# Business_Card5x.net
KiCad netlist of a schematic drawn in EAGLE
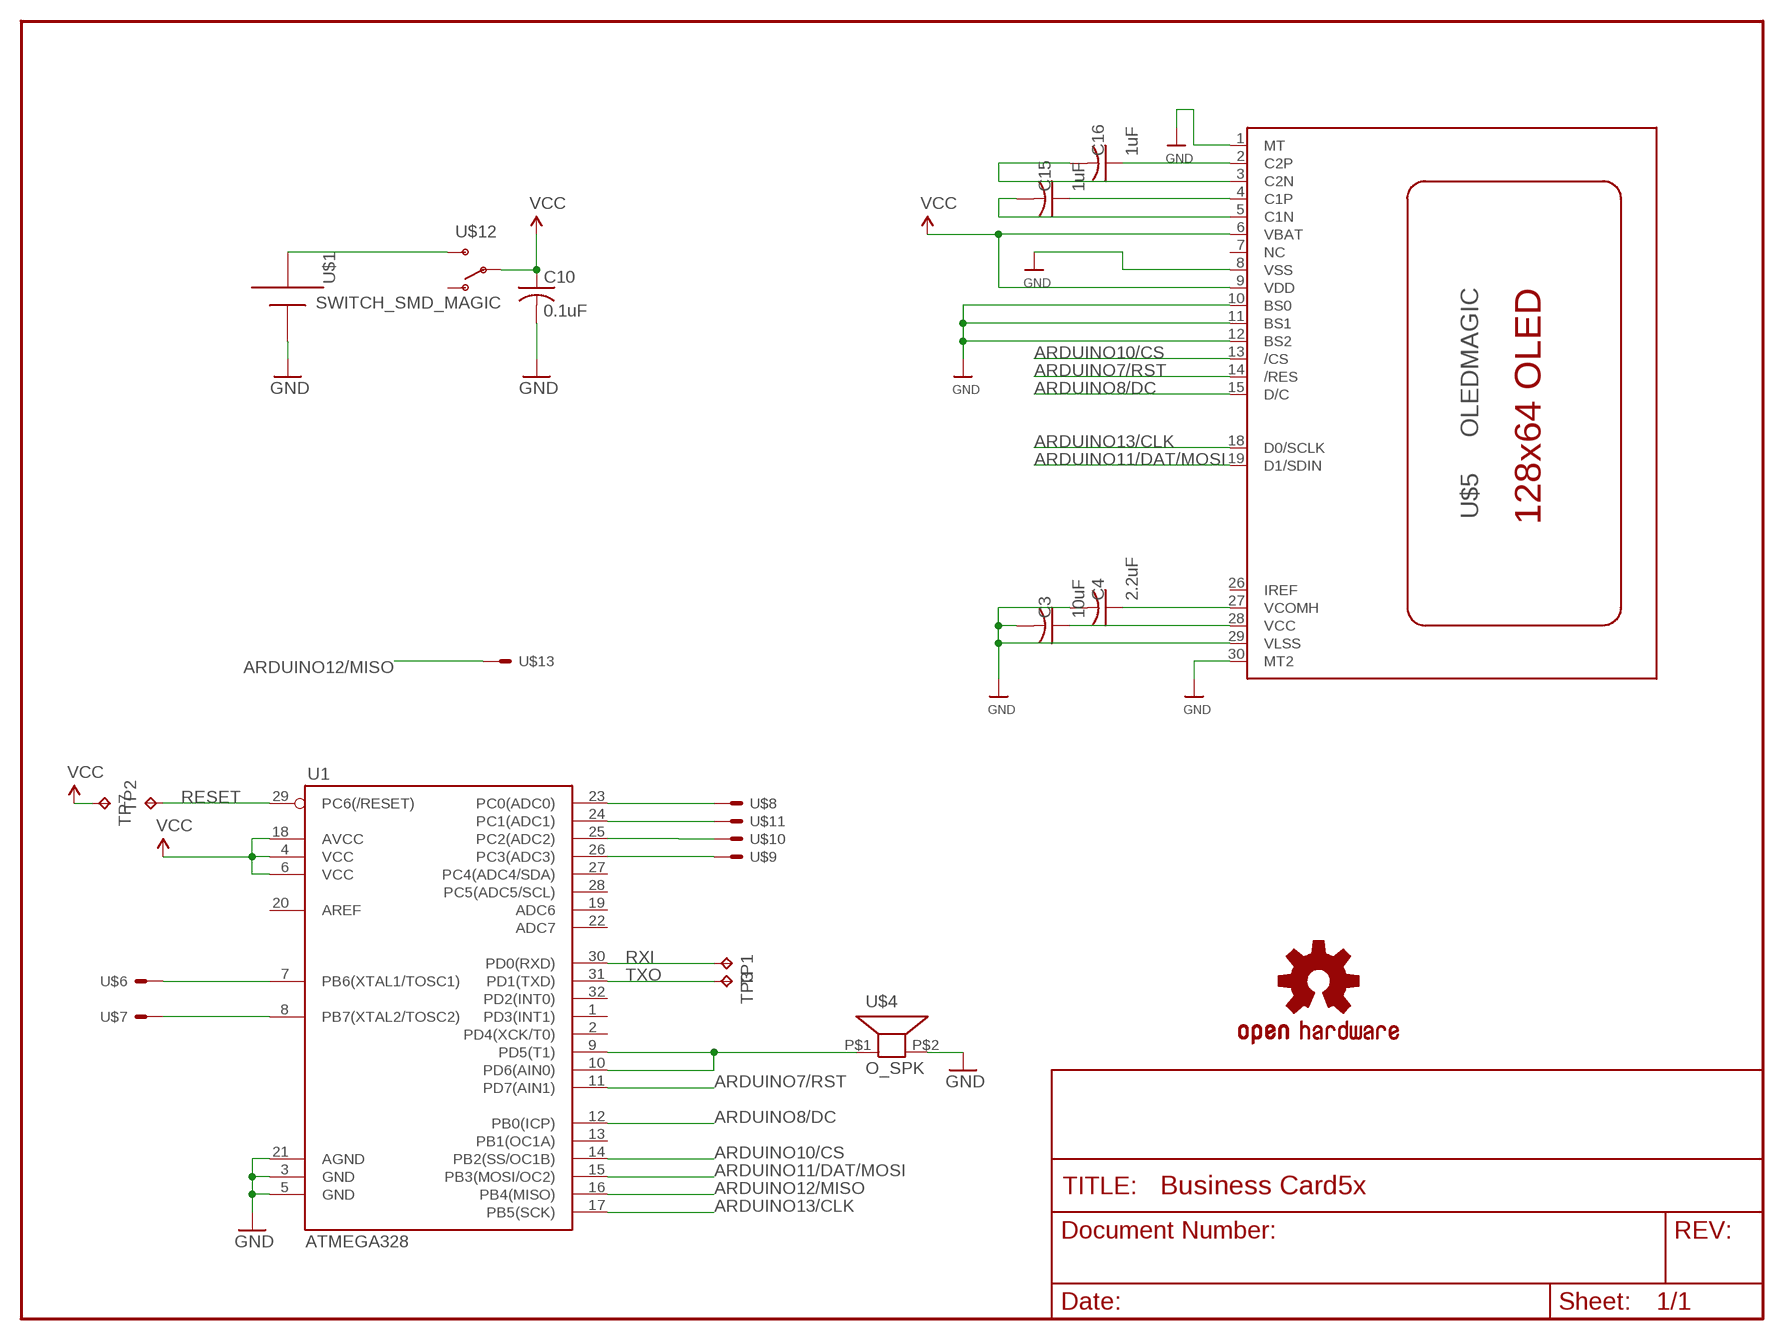
[diagram p0: schematic, sheet 1]

(export (version "E")
  (design (tool "Eeschema 10.0.6"))
  (components
    (comp (ref "C3")
      (value "10uF")
      (footprint "eagle-import:1MILCIR")
      (libsource (lib "eagle-import") (part "O_CAP0805"))
    )
    (comp (ref "C4")
      (value "2.2uF")
      (footprint "eagle-import:1MILCIR")
      (libsource (lib "eagle-import") (part "O_CAP0805"))
    )
    (comp (ref "C10")
      (value "0.1uF")
      (footprint "eagle-import:1MILCIR")
      (libsource (lib "eagle-import") (part "O_CAP0805"))
    )
    (comp (ref "C15")
      (value "1uF")
      (footprint "eagle-import:1MILCIR")
      (libsource (lib "eagle-import") (part "O_CAP0805"))
    )
    (comp (ref "C16")
      (value "1uF")
      (footprint "eagle-import:1MILCIR")
      (libsource (lib "eagle-import") (part "O_CAP0805"))
    )
    (comp (ref "TP1")
      (value "TPTP14R")
      (footprint "eagle-import:TP14R")
      (libsource (lib "eagle-import") (part "TPTP14R"))
    )
    (comp (ref "TP2")
      (value "TPTP14R")
      (footprint "eagle-import:TP14R")
      (libsource (lib "eagle-import") (part "TPTP14R"))
    )
    (comp (ref "TP3")
      (value "TPTP14R")
      (footprint "eagle-import:TP14R")
      (libsource (lib "eagle-import") (part "TPTP14R"))
    )
    (comp (ref "TP7")
      (value "TPTP08SQ")
      (footprint "eagle-import:TP08SQ")
      (libsource (lib "eagle-import") (part "TPTP08SQ"))
    )
    (comp (ref "U$1")
      (value "2016BAT")
      (footprint "eagle-import:CR2016")
      (libsource (lib "eagle-import") (part "2016BAT"))
    )
    (comp (ref "U$3")
      (value "OSHW-LOGOS")
      (footprint "eagle-import:OSHW-LOGO-S")
      (libsource (lib "eagle-import") (part "OSHW-LOGOS"))
    )
    (comp (ref "U$4")
      (value "O_SPK")
      (footprint "eagle-import:O_SPK")
      (libsource (lib "eagle-import") (part "O_SPK"))
    )
    (comp (ref "U$5")
      (value "OLEDMAGIC")
      (footprint "eagle-import:1X30OLED")
      (libsource (lib "eagle-import") (part "OLEDMAGIC"))
    )
    (comp (ref "U$6")
      (value "CAP_BUTTON")
      (footprint "eagle-import:CAPBUTTON")
      (libsource (lib "eagle-import") (part "CAP_BUTTON"))
    )
    (comp (ref "U$7")
      (value "CAP_BUTTON")
      (footprint "eagle-import:CAPBUTTON")
      (libsource (lib "eagle-import") (part "CAP_BUTTON"))
    )
    (comp (ref "U$8")
      (value "CAP_DPAD")
      (footprint "eagle-import:DPAD")
      (libsource (lib "eagle-import") (part "CAP_DPAD"))
    )
    (comp (ref "U$9")
      (value "CAP_DPAD")
      (footprint "eagle-import:DPAD")
      (libsource (lib "eagle-import") (part "CAP_DPAD"))
    )
    (comp (ref "U$10")
      (value "CAP_DPAD")
      (footprint "eagle-import:DPAD")
      (libsource (lib "eagle-import") (part "CAP_DPAD"))
    )
    (comp (ref "U$11")
      (value "CAP_DPAD")
      (footprint "eagle-import:DPAD")
      (libsource (lib "eagle-import") (part "CAP_DPAD"))
    )
    (comp (ref "U$12")
      (value "SWITCH_SMD_MAGIC")
      (footprint "eagle-import:SWITCH_SMD_SUNKEN")
      (libsource (lib "eagle-import") (part "SWITCH_SMD_MAGIC"))
    )
    (comp (ref "U$13")
      (value "VERT_TEST")
      (footprint "eagle-import:VERT_TEST")
      (libsource (lib "eagle-import") (part "VERT_TEST"))
    )
    (comp (ref "U1")
      (value "ATMEGA328")
      (footprint "eagle-import:TQFP32")
      (libsource (lib "eagle-import") (part "O_ATMEGA328_32"))
    )
  )
  (nets
    (net (code "1") (name "/ARDUINO7{slash}RST") (class "Default")
      (node (ref "U$5") (pin "14") (pinfunction "/RES_14") (pintype "input"))
      (node (ref "U1") (pin "11") (pinfunction "PD7(AIN1)_11") (pintype "bidirectional"))
    )
    (net (code "2") (name "/ARDUINO8{slash}DC") (class "Default")
      (node (ref "U$5") (pin "15") (pinfunction "D/C_15") (pintype "input"))
      (node (ref "U1") (pin "12") (pinfunction "PB0(ICP)_12") (pintype "bidirectional"))
    )
    (net (code "3") (name "/ARDUINO10{slash}CS") (class "Default")
      (node (ref "U$5") (pin "13") (pinfunction "/CS_13") (pintype "input"))
      (node (ref "U1") (pin "14") (pinfunction "PB2(SS/OC1B)_14") (pintype "bidirectional"))
    )
    (net (code "4") (name "/ARDUINO11{slash}DAT{slash}MOSI") (class "Default")
      (node (ref "U$5") (pin "19") (pinfunction "D1/SDIN_19") (pintype "bidirectional"))
      (node (ref "U1") (pin "15") (pinfunction "PB3(MOSI/OC2)_15") (pintype "bidirectional"))
    )
    (net (code "5") (name "/ARDUINO12{slash}MISO") (class "Default")
      (node (ref "U$13") (pin "P$1") (pinfunction "S_P$1") (pintype "passive"))
      (node (ref "U1") (pin "16") (pinfunction "PB4(MISO)_16") (pintype "bidirectional"))
    )
    (net (code "6") (name "/ARDUINO13{slash}CLK") (class "Default")
      (node (ref "U$5") (pin "18") (pinfunction "D0/SCLK_18") (pintype "bidirectional"))
      (node (ref "U1") (pin "17") (pinfunction "PB5(SCK)_17") (pintype "bidirectional"))
    )
    (net (code "7") (name "/RESET") (class "Default")
      (node (ref "TP2") (pin "TP") (pinfunction "TP_TP") (pintype "input"))
      (node (ref "U1") (pin "29") (pinfunction "PC6(/RESET)_29") (pintype "bidirectional"))
    )
    (net (code "8") (name "/RXI") (class "Default")
      (node (ref "TP1") (pin "TP") (pinfunction "TP_TP") (pintype "input"))
      (node (ref "U1") (pin "30") (pinfunction "PD0(RXD)_30") (pintype "bidirectional"))
    )
    (net (code "9") (name "/TXO") (class "Default")
      (node (ref "TP3") (pin "TP") (pinfunction "TP_TP") (pintype "input"))
      (node (ref "U1") (pin "31") (pinfunction "PD1(TXD)_31") (pintype "bidirectional"))
    )
    (net (code "10") (name "GND") (class "Default")
      (node (ref "C10") (pin "P$2") (pinfunction "2_P$2") (pintype "passive"))
      (node (ref "C3") (pin "P$2") (pinfunction "2_P$2") (pintype "passive"))
      (node (ref "C4") (pin "P$2") (pinfunction "2_P$2") (pintype "passive"))
      (node (ref "U$1") (pin "P$1") (pinfunction "+_P$1") (pintype "bidirectional"))
      (node (ref "U$4") (pin "P$2") (pinfunction "2_P$2") (pintype "passive"))
      (node (ref "U$5") (pin "1") (pinfunction "MT_1") (pintype "input"))
      (node (ref "U$5") (pin "10") (pinfunction "BS0_10") (pintype "input"))
      (node (ref "U$5") (pin "11") (pinfunction "BS1_11") (pintype "input"))
      (node (ref "U$5") (pin "12") (pinfunction "BS2_12") (pintype "input"))
      (node (ref "U$5") (pin "29") (pinfunction "VLSS_29") (pintype "power_in"))
      (node (ref "U$5") (pin "30") (pinfunction "MT2_30") (pintype "input"))
      (node (ref "U$5") (pin "8") (pinfunction "VSS_8") (pintype "power_in"))
      (node (ref "U1") (pin "21") (pinfunction "AGND_21") (pintype "bidirectional"))
      (node (ref "U1") (pin "3") (pinfunction "GND_3") (pintype "bidirectional"))
      (node (ref "U1") (pin "5") (pinfunction "GND_5") (pintype "bidirectional"))
    )
    (net (code "11") (name "Net-(C3-1)") (class "Default")
      (node (ref "C3") (pin "P$1") (pinfunction "1_P$1") (pintype "passive"))
      (node (ref "U$5") (pin "28") (pinfunction "VCC_28") (pintype "power_in"))
    )
    (net (code "12") (name "Net-(C4-1)") (class "Default")
      (node (ref "C4") (pin "P$1") (pinfunction "1_P$1") (pintype "passive"))
      (node (ref "U$5") (pin "27") (pinfunction "VCOMH_27") (pintype "output"))
    )
    (net (code "13") (name "Net-(C15-1)") (class "Default")
      (node (ref "C15") (pin "P$1") (pinfunction "1_P$1") (pintype "passive"))
      (node (ref "U$5") (pin "4") (pinfunction "C1P_4") (pintype "input"))
    )
    (net (code "14") (name "Net-(C15-2)") (class "Default")
      (node (ref "C15") (pin "P$2") (pinfunction "2_P$2") (pintype "passive"))
      (node (ref "U$5") (pin "5") (pinfunction "C1N_5") (pintype "input"))
    )
    (net (code "15") (name "Net-(C16-1)") (class "Default")
      (node (ref "C16") (pin "P$1") (pinfunction "1_P$1") (pintype "passive"))
      (node (ref "U$5") (pin "2") (pinfunction "C2P_2") (pintype "input"))
    )
    (net (code "16") (name "Net-(C16-2)") (class "Default")
      (node (ref "C16") (pin "P$2") (pinfunction "2_P$2") (pintype "passive"))
      (node (ref "U$5") (pin "3") (pinfunction "C2N_3") (pintype "input"))
    )
    (net (code "17") (name "Net-(U$1--)") (class "Default")
      (node (ref "U$1") (pin "P$2") (pinfunction "-_P$2") (pintype "bidirectional"))
      (node (ref "U$12") (pin "3") (pinfunction "S_3") (pintype "passive"))
    )
    (net (code "18") (name "Net-(U$4-1)") (class "Default")
      (node (ref "U$4") (pin "P$1") (pinfunction "1_P$1") (pintype "passive"))
      (node (ref "U1") (pin "10") (pinfunction "PD6(AIN0)_10") (pintype "bidirectional"))
      (node (ref "U1") (pin "9") (pinfunction "PD5(T1)_9") (pintype "bidirectional"))
    )
    (net (code "19") (name "Net-(U$8-S)") (class "Default")
      (node (ref "U$8") (pin "P$1") (pinfunction "S_P$1") (pintype "passive"))
      (node (ref "U1") (pin "23") (pinfunction "PC0(ADC0)_23") (pintype "bidirectional"))
    )
    (net (code "20") (name "Net-(U$9-S)") (class "Default")
      (node (ref "U$9") (pin "P$1") (pinfunction "S_P$1") (pintype "passive"))
      (node (ref "U1") (pin "26") (pinfunction "PC3(ADC3)_26") (pintype "bidirectional"))
    )
    (net (code "21") (name "Net-(U$10-S)") (class "Default")
      (node (ref "U$10") (pin "P$1") (pinfunction "S_P$1") (pintype "passive"))
      (node (ref "U1") (pin "25") (pinfunction "PC2(ADC2)_25") (pintype "bidirectional"))
    )
    (net (code "22") (name "Net-(U$11-S)") (class "Default")
      (node (ref "U$11") (pin "P$1") (pinfunction "S_P$1") (pintype "passive"))
      (node (ref "U1") (pin "24") (pinfunction "PC1(ADC1)_24") (pintype "bidirectional"))
    )
    (net (code "23") (name "Net-(U1-PB6(XTAL1{slash}TOSC1))") (class "Default")
      (node (ref "U$6") (pin "P$1") (pinfunction "S_P$1") (pintype "passive"))
      (node (ref "U$6") (pin "P$2") (pinfunction "S_P$2") (pintype "passive"))
      (node (ref "U1") (pin "7") (pinfunction "PB6(XTAL1/TOSC1)_7") (pintype "bidirectional"))
    )
    (net (code "24") (name "Net-(U1-PB7(XTAL2{slash}TOSC2))") (class "Default")
      (node (ref "U$7") (pin "P$1") (pinfunction "S_P$1") (pintype "passive"))
      (node (ref "U$7") (pin "P$2") (pinfunction "S_P$2") (pintype "passive"))
      (node (ref "U1") (pin "8") (pinfunction "PB7(XTAL2/TOSC2)_8") (pintype "bidirectional"))
    )
    (net (code "25") (name "VCC") (class "Default")
      (node (ref "C10") (pin "P$1") (pinfunction "1_P$1") (pintype "passive"))
      (node (ref "TP7") (pin "TP") (pinfunction "TP_TP") (pintype "input"))
      (node (ref "U$12") (pin "2") (pinfunction "P_2") (pintype "passive"))
      (node (ref "U$5") (pin "6") (pinfunction "VBAT_6") (pintype "input"))
      (node (ref "U$5") (pin "9") (pinfunction "VDD_9") (pintype "power_in"))
      (node (ref "U1") (pin "18") (pinfunction "AVCC_18") (pintype "bidirectional"))
      (node (ref "U1") (pin "4") (pinfunction "VCC_4") (pintype "bidirectional"))
      (node (ref "U1") (pin "6") (pinfunction "VCC_6") (pintype "bidirectional"))
    )
    (net (code "26") (name "unconnected-(U$5-IREF-Pad26)") (class "Default")
      (node (ref "U$5") (pin "26") (pinfunction "IREF_26") (pintype "input"))
    )
    (net (code "27") (name "unconnected-(U$5-NC-Pad7)") (class "Default")
      (node (ref "U$5") (pin "7") (pinfunction "NC_7") (pintype "no_connect"))
    )
    (net (code "28") (name "unconnected-(U$12-O-Pad1)") (class "Default")
      (node (ref "U$12") (pin "1") (pinfunction "O_1") (pintype "passive"))
    )
    (net (code "29") (name "unconnected-(U1-ADC6-Pad19)") (class "Default")
      (node (ref "U1") (pin "19") (pinfunction "ADC6_19") (pintype "bidirectional"))
    )
    (net (code "30") (name "unconnected-(U1-ADC7-Pad22)") (class "Default")
      (node (ref "U1") (pin "22") (pinfunction "ADC7_22") (pintype "bidirectional"))
    )
    (net (code "31") (name "unconnected-(U1-AREF-Pad20)") (class "Default")
      (node (ref "U1") (pin "20") (pinfunction "AREF_20") (pintype "bidirectional"))
    )
    (net (code "32") (name "unconnected-(U1-PB1(OC1A)-Pad13)") (class "Default")
      (node (ref "U1") (pin "13") (pinfunction "PB1(OC1A)_13") (pintype "bidirectional"))
    )
    (net (code "33") (name "unconnected-(U1-PC4(ADC4{slash}SDA)-Pad27)") (class "Default")
      (node (ref "U1") (pin "27") (pinfunction "PC4(ADC4/SDA)_27") (pintype "bidirectional"))
    )
    (net (code "34") (name "unconnected-(U1-PC5(ADC5{slash}SCL)-Pad28)") (class "Default")
      (node (ref "U1") (pin "28") (pinfunction "PC5(ADC5/SCL)_28") (pintype "bidirectional"))
    )
    (net (code "35") (name "unconnected-(U1-PD2(INT0)-Pad32)") (class "Default")
      (node (ref "U1") (pin "32") (pinfunction "PD2(INT0)_32") (pintype "bidirectional"))
    )
    (net (code "36") (name "unconnected-(U1-PD3(INT1)-Pad1)") (class "Default")
      (node (ref "U1") (pin "1") (pinfunction "PD3(INT1)_1") (pintype "bidirectional"))
    )
    (net (code "37") (name "unconnected-(U1-PD4(XCK{slash}T0)-Pad2)") (class "Default")
      (node (ref "U1") (pin "2") (pinfunction "PD4(XCK/T0)_2") (pintype "bidirectional"))
    )
  )
)
